# Main_BoardV2.net
KiCad netlist of a schematic drawn in EAGLE
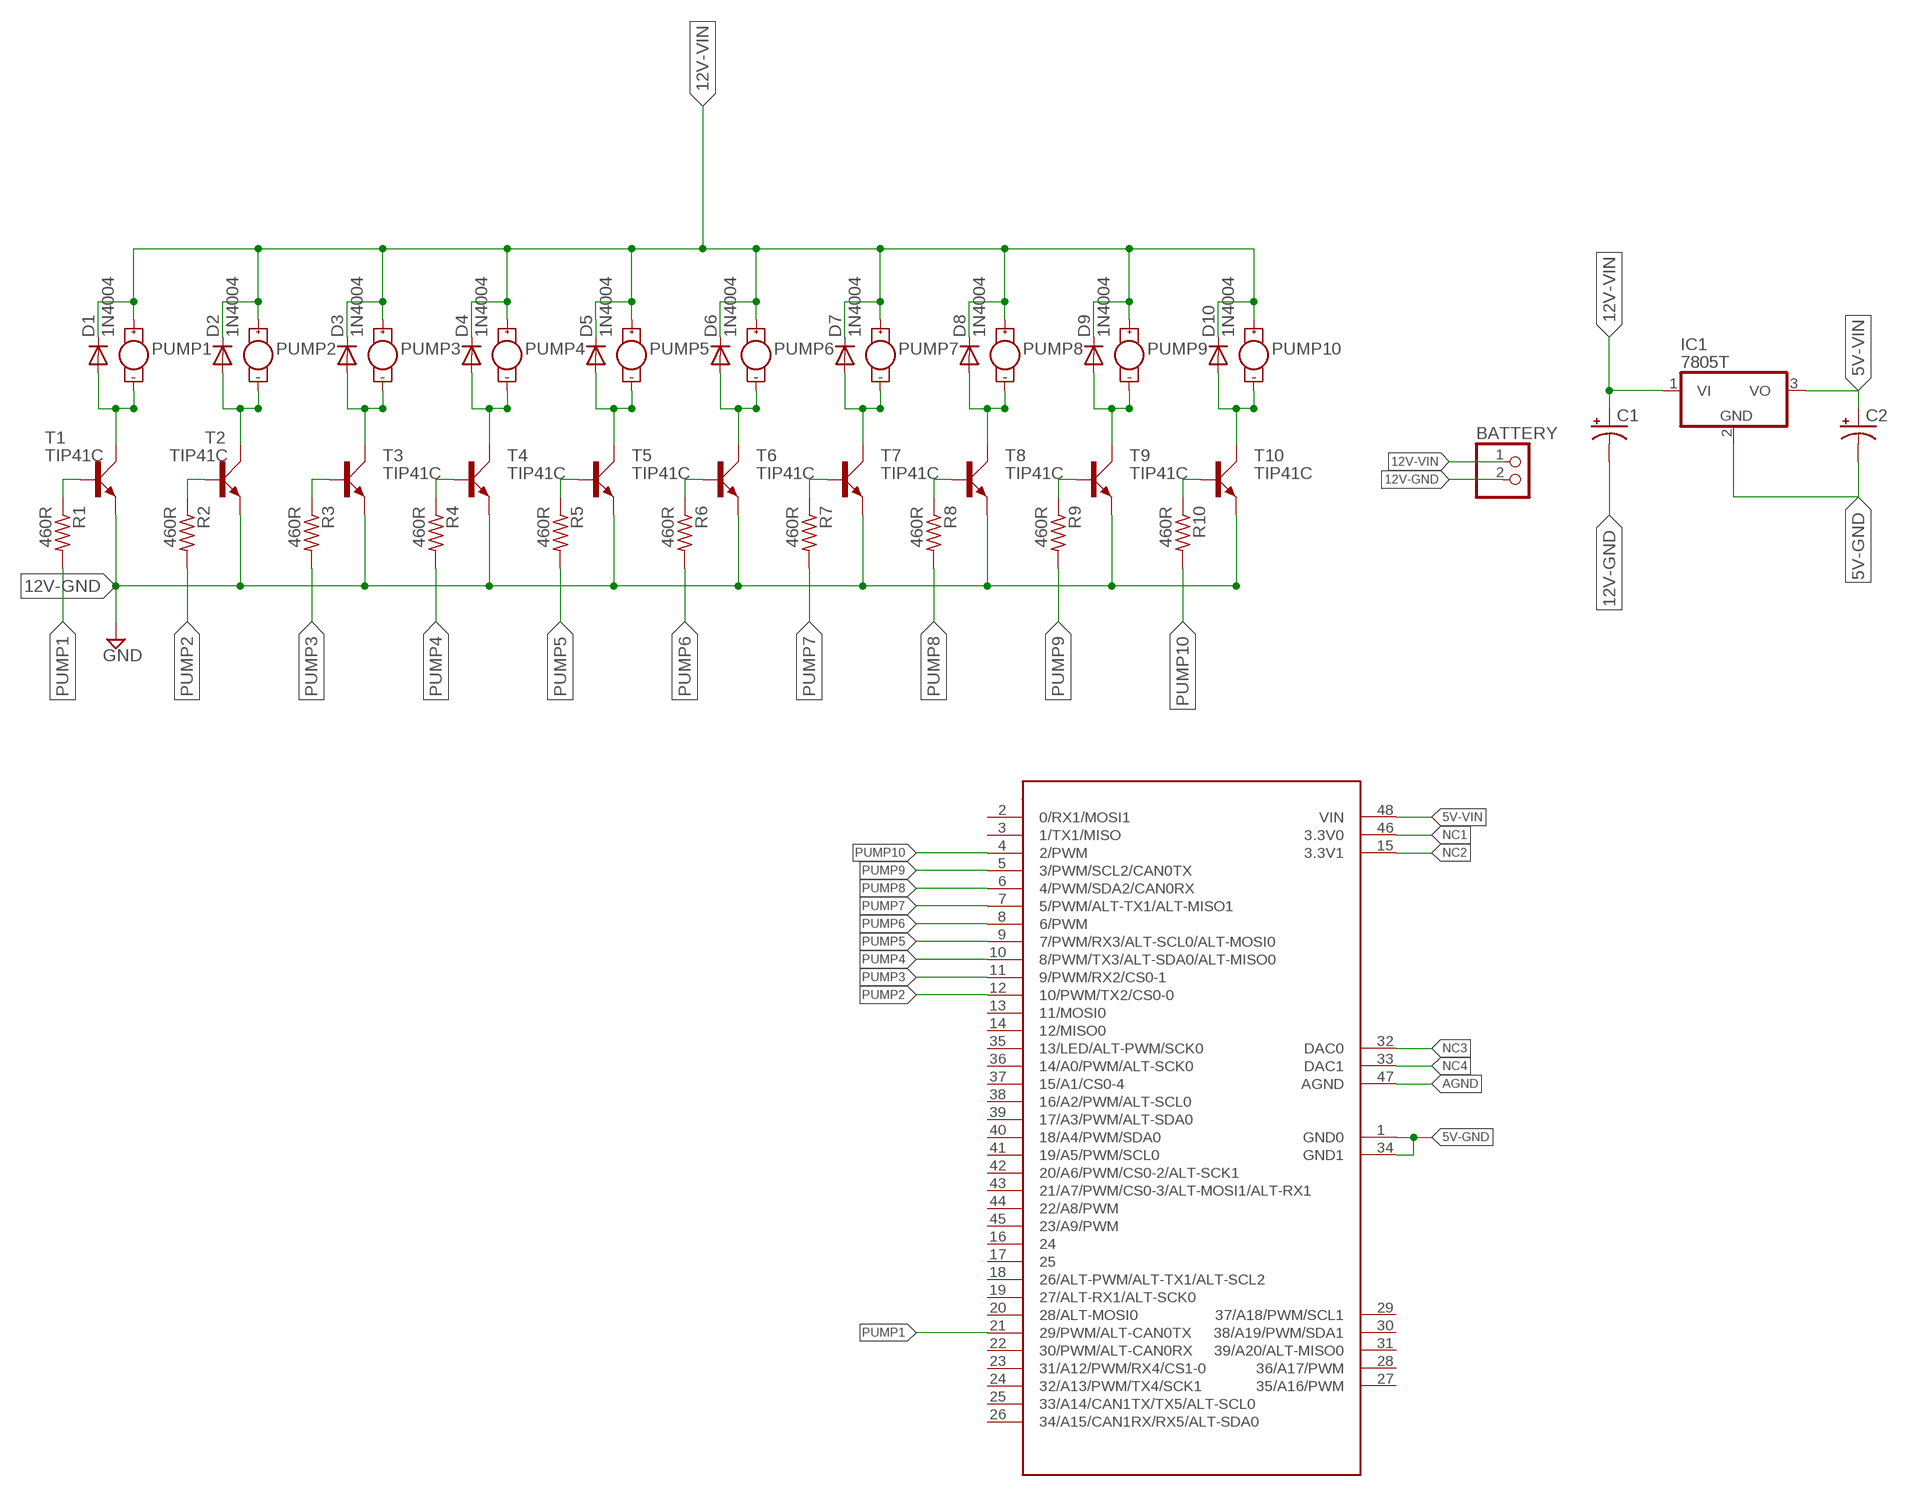
[diagram p0: schematic, sheet 1]

(export (version "E")
  (design (tool "Eeschema 10.0.6"))
  (components
    (comp (ref "BATTERY")
      (value "PINHD-1X2")
      (footprint "eagle-import:1X02")
      (fields (field (name "SPICEPREFIX") "B"))
      (libsource (lib "eagle-import") (part "PINHD-1X2"))
    )
    (comp (ref "C1")
      (value "CPOL-USE5-10.5")
      (footprint "eagle-import:E5-10,5")
      (libsource (lib "eagle-import") (part "CPOL-USE5-10.5"))
    )
    (comp (ref "C2")
      (value "CPOL-USE2.5-5")
      (footprint "eagle-import:E2,5-5")
      (libsource (lib "eagle-import") (part "CPOL-USE2.5-5"))
    )
    (comp (ref "D1")
      (value "1N4004")
      (footprint "eagle-import:DO41-10")
      (libsource (lib "eagle-import") (part "1N4004"))
    )
    (comp (ref "D2")
      (value "1N4004")
      (footprint "eagle-import:DO41-10")
      (libsource (lib "eagle-import") (part "1N4004"))
    )
    (comp (ref "D3")
      (value "1N4004")
      (footprint "eagle-import:DO41-10")
      (libsource (lib "eagle-import") (part "1N4004"))
    )
    (comp (ref "D4")
      (value "1N4004")
      (footprint "eagle-import:DO41-10")
      (libsource (lib "eagle-import") (part "1N4004"))
    )
    (comp (ref "D5")
      (value "1N4004")
      (footprint "eagle-import:DO41-10")
      (libsource (lib "eagle-import") (part "1N4004"))
    )
    (comp (ref "D6")
      (value "1N4004")
      (footprint "eagle-import:DO41-10")
      (libsource (lib "eagle-import") (part "1N4004"))
    )
    (comp (ref "D7")
      (value "1N4004")
      (footprint "eagle-import:DO41-10")
      (libsource (lib "eagle-import") (part "1N4004"))
    )
    (comp (ref "D8")
      (value "1N4004")
      (footprint "eagle-import:DO41-10")
      (libsource (lib "eagle-import") (part "1N4004"))
    )
    (comp (ref "D9")
      (value "1N4004")
      (footprint "eagle-import:DO41-10")
      (libsource (lib "eagle-import") (part "1N4004"))
    )
    (comp (ref "D10")
      (value "1N4004")
      (footprint "eagle-import:DO41-10")
      (libsource (lib "eagle-import") (part "1N4004"))
    )
    (comp (ref "IC1")
      (value "7805T")
      (footprint "eagle-import:TO220H")
      (libsource (lib "eagle-import") (part "78T05"))
    )
    (comp (ref "PUMP1")
      (value "PUMPS")
      (footprint "eagle-import:1X2_HEADER")
      (libsource (lib "eagle-import") (part "PUMPS"))
    )
    (comp (ref "PUMP2")
      (value "PUMPS")
      (footprint "eagle-import:1X2_HEADER")
      (libsource (lib "eagle-import") (part "PUMPS"))
    )
    (comp (ref "PUMP3")
      (value "PUMPS")
      (footprint "eagle-import:1X2_HEADER")
      (libsource (lib "eagle-import") (part "PUMPS"))
    )
    (comp (ref "PUMP4")
      (value "PUMPS")
      (footprint "eagle-import:1X2_HEADER")
      (libsource (lib "eagle-import") (part "PUMPS"))
    )
    (comp (ref "PUMP5")
      (value "PUMPS")
      (footprint "eagle-import:1X2_HEADER")
      (libsource (lib "eagle-import") (part "PUMPS"))
    )
    (comp (ref "PUMP6")
      (value "PUMPS")
      (footprint "eagle-import:1X2_HEADER")
      (libsource (lib "eagle-import") (part "PUMPS"))
    )
    (comp (ref "PUMP7")
      (value "PUMPS")
      (footprint "eagle-import:1X2_HEADER")
      (libsource (lib "eagle-import") (part "PUMPS"))
    )
    (comp (ref "PUMP8")
      (value "PUMPS")
      (footprint "eagle-import:1X2_HEADER")
      (libsource (lib "eagle-import") (part "PUMPS"))
    )
    (comp (ref "PUMP9")
      (value "PUMPS")
      (footprint "eagle-import:1X2_HEADER")
      (libsource (lib "eagle-import") (part "PUMPS"))
    )
    (comp (ref "PUMP10")
      (value "PUMPS")
      (footprint "eagle-import:1X2_HEADER")
      (libsource (lib "eagle-import") (part "PUMPS"))
    )
    (comp (ref "R1")
      (value "460R")
      (footprint "eagle-import:0805-THM")
      (libsource (lib "eagle-import") (part "R-US_FLIPFLOP"))
    )
    (comp (ref "R2")
      (value "460R")
      (footprint "eagle-import:0805-THM")
      (libsource (lib "eagle-import") (part "R-US_FLIPFLOP"))
    )
    (comp (ref "R3")
      (value "460R")
      (footprint "eagle-import:0805-THM")
      (libsource (lib "eagle-import") (part "R-US_FLIPFLOP"))
    )
    (comp (ref "R4")
      (value "460R")
      (footprint "eagle-import:0805-THM")
      (libsource (lib "eagle-import") (part "R-US_FLIPFLOP"))
    )
    (comp (ref "R5")
      (value "460R")
      (footprint "eagle-import:0805-THM")
      (libsource (lib "eagle-import") (part "R-US_FLIPFLOP"))
    )
    (comp (ref "R6")
      (value "460R")
      (footprint "eagle-import:0805-THM")
      (libsource (lib "eagle-import") (part "R-US_FLIPFLOP"))
    )
    (comp (ref "R7")
      (value "460R")
      (footprint "eagle-import:0805-THM")
      (libsource (lib "eagle-import") (part "R-US_FLIPFLOP"))
    )
    (comp (ref "R8")
      (value "460R")
      (footprint "eagle-import:0805-THM")
      (libsource (lib "eagle-import") (part "R-US_FLIPFLOP"))
    )
    (comp (ref "R9")
      (value "460R")
      (footprint "eagle-import:0805-THM")
      (libsource (lib "eagle-import") (part "R-US_FLIPFLOP"))
    )
    (comp (ref "R10")
      (value "460R")
      (footprint "eagle-import:0805-THM")
      (libsource (lib "eagle-import") (part "R-US_FLIPFLOP"))
    )
    (comp (ref "T1")
      (value "TIP41C")
      (footprint "eagle-import:TO220AV")
      (libsource (lib "eagle-import") (part "TIP41C"))
    )
    (comp (ref "T2")
      (value "TIP41C")
      (footprint "eagle-import:TO220AV")
      (libsource (lib "eagle-import") (part "TIP41C"))
    )
    (comp (ref "T3")
      (value "TIP41C")
      (footprint "eagle-import:TO220AV")
      (libsource (lib "eagle-import") (part "TIP41C"))
    )
    (comp (ref "T4")
      (value "TIP41C")
      (footprint "eagle-import:TO220AV")
      (libsource (lib "eagle-import") (part "TIP41C"))
    )
    (comp (ref "T5")
      (value "TIP41C")
      (footprint "eagle-import:TO220AV")
      (libsource (lib "eagle-import") (part "TIP41C"))
    )
    (comp (ref "T6")
      (value "TIP41C")
      (footprint "eagle-import:TO220AV")
      (libsource (lib "eagle-import") (part "TIP41C"))
    )
    (comp (ref "T7")
      (value "TIP41C")
      (footprint "eagle-import:TO220AV")
      (libsource (lib "eagle-import") (part "TIP41C"))
    )
    (comp (ref "T8")
      (value "TIP41C")
      (footprint "eagle-import:TO220AV")
      (libsource (lib "eagle-import") (part "TIP41C"))
    )
    (comp (ref "T9")
      (value "TIP41C")
      (footprint "eagle-import:TO220AV")
      (libsource (lib "eagle-import") (part "TIP41C"))
    )
    (comp (ref "T10")
      (value "TIP41C")
      (footprint "eagle-import:TO220AV")
      (libsource (lib "eagle-import") (part "TIP41C"))
    )
    (comp (ref "TEENSY1")
      (value "TEENSY_3.5")
      (footprint "eagle-import:DIP1524W60P254L6350H635Q48A")
      (libsource (lib "eagle-import") (part "TEENSY_3.5"))
    )
  )
  (nets
    (net (code "1") (name "5V-GND") (class "Default")
      (node (ref "C2") (pin "-") (pinfunction "-_-") (pintype "passive"))
      (node (ref "IC1") (pin "2") (pinfunction "GND_2") (pintype "passive"))
      (node (ref "TEENSY1") (pin "1") (pinfunction "GND0_1") (pintype "power_in"))
      (node (ref "TEENSY1") (pin "34") (pinfunction "GND1_34") (pintype "power_in"))
    )
    (net (code "2") (name "5V-VIN") (class "Default")
      (node (ref "C2") (pin "+") (pinfunction "+_+") (pintype "passive"))
      (node (ref "IC1") (pin "3") (pinfunction "VO_3") (pintype "passive"))
      (node (ref "TEENSY1") (pin "48") (pinfunction "VIN_48") (pintype "power_in"))
    )
    (net (code "3") (name "12V-GND") (class "Default")
      (node (ref "BATTERY") (pin "2") (pinfunction "2_2") (pintype "passive"))
      (node (ref "C1") (pin "-") (pinfunction "-_-") (pintype "passive"))
      (node (ref "T1") (pin "E") (pinfunction "E_E") (pintype "passive"))
      (node (ref "T10") (pin "E") (pinfunction "E_E") (pintype "passive"))
      (node (ref "T2") (pin "E") (pinfunction "E_E") (pintype "passive"))
      (node (ref "T3") (pin "E") (pinfunction "E_E") (pintype "passive"))
      (node (ref "T4") (pin "E") (pinfunction "E_E") (pintype "passive"))
      (node (ref "T5") (pin "E") (pinfunction "E_E") (pintype "passive"))
      (node (ref "T6") (pin "E") (pinfunction "E_E") (pintype "passive"))
      (node (ref "T7") (pin "E") (pinfunction "E_E") (pintype "passive"))
      (node (ref "T8") (pin "E") (pinfunction "E_E") (pintype "passive"))
      (node (ref "T9") (pin "E") (pinfunction "E_E") (pintype "passive"))
    )
    (net (code "4") (name "12V-VIN") (class "Default")
      (node (ref "BATTERY") (pin "1") (pinfunction "1_1") (pintype "passive"))
      (node (ref "C1") (pin "+") (pinfunction "+_+") (pintype "passive"))
      (node (ref "D1") (pin "C") (pinfunction "C_C") (pintype "passive"))
      (node (ref "D10") (pin "C") (pinfunction "C_C") (pintype "passive"))
      (node (ref "D2") (pin "C") (pinfunction "C_C") (pintype "passive"))
      (node (ref "D3") (pin "C") (pinfunction "C_C") (pintype "passive"))
      (node (ref "D4") (pin "C") (pinfunction "C_C") (pintype "passive"))
      (node (ref "D5") (pin "C") (pinfunction "C_C") (pintype "passive"))
      (node (ref "D6") (pin "C") (pinfunction "C_C") (pintype "passive"))
      (node (ref "D7") (pin "C") (pinfunction "C_C") (pintype "passive"))
      (node (ref "D8") (pin "C") (pinfunction "C_C") (pintype "passive"))
      (node (ref "D9") (pin "C") (pinfunction "C_C") (pintype "passive"))
      (node (ref "IC1") (pin "1") (pinfunction "VI_1") (pintype "input"))
      (node (ref "PUMP1") (pin "1") (pinfunction "+_1") (pintype "bidirectional"))
      (node (ref "PUMP10") (pin "1") (pinfunction "+_1") (pintype "bidirectional"))
      (node (ref "PUMP2") (pin "1") (pinfunction "+_1") (pintype "bidirectional"))
      (node (ref "PUMP3") (pin "1") (pinfunction "+_1") (pintype "bidirectional"))
      (node (ref "PUMP4") (pin "1") (pinfunction "+_1") (pintype "bidirectional"))
      (node (ref "PUMP5") (pin "1") (pinfunction "+_1") (pintype "bidirectional"))
      (node (ref "PUMP6") (pin "1") (pinfunction "+_1") (pintype "bidirectional"))
      (node (ref "PUMP7") (pin "1") (pinfunction "+_1") (pintype "bidirectional"))
      (node (ref "PUMP8") (pin "1") (pinfunction "+_1") (pintype "bidirectional"))
      (node (ref "PUMP9") (pin "1") (pinfunction "+_1") (pintype "bidirectional"))
    )
    (net (code "5") (name "AGND") (class "Default")
      (node (ref "TEENSY1") (pin "47") (pinfunction "AGND_47") (pintype "power_in"))
    )
    (net (code "6") (name "NC1") (class "Default")
      (node (ref "TEENSY1") (pin "46") (pinfunction "3.3V0_46") (pintype "power_in"))
    )
    (net (code "7") (name "NC2") (class "Default")
      (node (ref "TEENSY1") (pin "15") (pinfunction "3.3V1_15") (pintype "power_in"))
    )
    (net (code "8") (name "NC3") (class "Default")
      (node (ref "TEENSY1") (pin "32") (pinfunction "DAC0_32") (pintype "bidirectional"))
    )
    (net (code "9") (name "NC4") (class "Default")
      (node (ref "TEENSY1") (pin "33") (pinfunction "DAC1_33") (pintype "bidirectional"))
    )
    (net (code "10") (name "Net-(PUMP1--)") (class "Default")
      (node (ref "D1") (pin "A") (pinfunction "A_A") (pintype "passive"))
      (node (ref "PUMP1") (pin "2") (pinfunction "-_2") (pintype "bidirectional"))
      (node (ref "T1") (pin "C") (pinfunction "C_C") (pintype "passive"))
    )
    (net (code "11") (name "Net-(PUMP2--)") (class "Default")
      (node (ref "D2") (pin "A") (pinfunction "A_A") (pintype "passive"))
      (node (ref "PUMP2") (pin "2") (pinfunction "-_2") (pintype "bidirectional"))
      (node (ref "T2") (pin "C") (pinfunction "C_C") (pintype "passive"))
    )
    (net (code "12") (name "Net-(PUMP3--)") (class "Default")
      (node (ref "D3") (pin "A") (pinfunction "A_A") (pintype "passive"))
      (node (ref "PUMP3") (pin "2") (pinfunction "-_2") (pintype "bidirectional"))
      (node (ref "T3") (pin "C") (pinfunction "C_C") (pintype "passive"))
    )
    (net (code "13") (name "Net-(PUMP4--)") (class "Default")
      (node (ref "D4") (pin "A") (pinfunction "A_A") (pintype "passive"))
      (node (ref "PUMP4") (pin "2") (pinfunction "-_2") (pintype "bidirectional"))
      (node (ref "T4") (pin "C") (pinfunction "C_C") (pintype "passive"))
    )
    (net (code "14") (name "Net-(PUMP5--)") (class "Default")
      (node (ref "D5") (pin "A") (pinfunction "A_A") (pintype "passive"))
      (node (ref "PUMP5") (pin "2") (pinfunction "-_2") (pintype "bidirectional"))
      (node (ref "T5") (pin "C") (pinfunction "C_C") (pintype "passive"))
    )
    (net (code "15") (name "Net-(PUMP6--)") (class "Default")
      (node (ref "D6") (pin "A") (pinfunction "A_A") (pintype "passive"))
      (node (ref "PUMP6") (pin "2") (pinfunction "-_2") (pintype "bidirectional"))
      (node (ref "T6") (pin "C") (pinfunction "C_C") (pintype "passive"))
    )
    (net (code "16") (name "Net-(PUMP7--)") (class "Default")
      (node (ref "D7") (pin "A") (pinfunction "A_A") (pintype "passive"))
      (node (ref "PUMP7") (pin "2") (pinfunction "-_2") (pintype "bidirectional"))
      (node (ref "T7") (pin "C") (pinfunction "C_C") (pintype "passive"))
    )
    (net (code "17") (name "Net-(PUMP8--)") (class "Default")
      (node (ref "D8") (pin "A") (pinfunction "A_A") (pintype "passive"))
      (node (ref "PUMP8") (pin "2") (pinfunction "-_2") (pintype "bidirectional"))
      (node (ref "T8") (pin "C") (pinfunction "C_C") (pintype "passive"))
    )
    (net (code "18") (name "Net-(PUMP9--)") (class "Default")
      (node (ref "D9") (pin "A") (pinfunction "A_A") (pintype "passive"))
      (node (ref "PUMP9") (pin "2") (pinfunction "-_2") (pintype "bidirectional"))
      (node (ref "T9") (pin "C") (pinfunction "C_C") (pintype "passive"))
    )
    (net (code "19") (name "Net-(PUMP10--)") (class "Default")
      (node (ref "D10") (pin "A") (pinfunction "A_A") (pintype "passive"))
      (node (ref "PUMP10") (pin "2") (pinfunction "-_2") (pintype "bidirectional"))
      (node (ref "T10") (pin "C") (pinfunction "C_C") (pintype "passive"))
    )
    (net (code "20") (name "Net-(R1-Pad1)") (class "Default")
      (node (ref "R1") (pin "1") (pinfunction "1_1") (pintype "passive"))
      (node (ref "T1") (pin "B") (pinfunction "B_B") (pintype "passive"))
    )
    (net (code "21") (name "Net-(R2-Pad1)") (class "Default")
      (node (ref "R2") (pin "1") (pinfunction "1_1") (pintype "passive"))
      (node (ref "T2") (pin "B") (pinfunction "B_B") (pintype "passive"))
    )
    (net (code "22") (name "Net-(R3-Pad1)") (class "Default")
      (node (ref "R3") (pin "1") (pinfunction "1_1") (pintype "passive"))
      (node (ref "T3") (pin "B") (pinfunction "B_B") (pintype "passive"))
    )
    (net (code "23") (name "Net-(R4-Pad1)") (class "Default")
      (node (ref "R4") (pin "1") (pinfunction "1_1") (pintype "passive"))
      (node (ref "T4") (pin "B") (pinfunction "B_B") (pintype "passive"))
    )
    (net (code "24") (name "Net-(R5-Pad1)") (class "Default")
      (node (ref "R5") (pin "1") (pinfunction "1_1") (pintype "passive"))
      (node (ref "T5") (pin "B") (pinfunction "B_B") (pintype "passive"))
    )
    (net (code "25") (name "Net-(R6-Pad1)") (class "Default")
      (node (ref "R6") (pin "1") (pinfunction "1_1") (pintype "passive"))
      (node (ref "T6") (pin "B") (pinfunction "B_B") (pintype "passive"))
    )
    (net (code "26") (name "Net-(R7-Pad1)") (class "Default")
      (node (ref "R7") (pin "1") (pinfunction "1_1") (pintype "passive"))
      (node (ref "T7") (pin "B") (pinfunction "B_B") (pintype "passive"))
    )
    (net (code "27") (name "Net-(R8-Pad1)") (class "Default")
      (node (ref "R8") (pin "1") (pinfunction "1_1") (pintype "passive"))
      (node (ref "T8") (pin "B") (pinfunction "B_B") (pintype "passive"))
    )
    (net (code "28") (name "Net-(R9-Pad1)") (class "Default")
      (node (ref "R9") (pin "1") (pinfunction "1_1") (pintype "passive"))
      (node (ref "T9") (pin "B") (pinfunction "B_B") (pintype "passive"))
    )
    (net (code "29") (name "Net-(R10-Pad1)") (class "Default")
      (node (ref "R10") (pin "1") (pinfunction "1_1") (pintype "passive"))
      (node (ref "T10") (pin "B") (pinfunction "B_B") (pintype "passive"))
    )
    (net (code "30") (name "PUMP1") (class "Default")
      (node (ref "R1") (pin "2") (pinfunction "2_2") (pintype "passive"))
      (node (ref "TEENSY1") (pin "21") (pinfunction "29/PWM/ALT-CAN0TX_21") (pintype "bidirectional"))
    )
    (net (code "31") (name "PUMP2") (class "Default")
      (node (ref "R2") (pin "2") (pinfunction "2_2") (pintype "passive"))
      (node (ref "TEENSY1") (pin "12") (pinfunction "10/PWM/TX2/CS0-0_12") (pintype "bidirectional"))
    )
    (net (code "32") (name "PUMP3") (class "Default")
      (node (ref "R3") (pin "2") (pinfunction "2_2") (pintype "passive"))
      (node (ref "TEENSY1") (pin "11") (pinfunction "9/PWM/RX2/CS0-1_11") (pintype "bidirectional"))
    )
    (net (code "33") (name "PUMP4") (class "Default")
      (node (ref "R4") (pin "2") (pinfunction "2_2") (pintype "passive"))
      (node (ref "TEENSY1") (pin "10") (pinfunction "8/PWM/TX3/ALT-SDA0/ALT-MISO0_10") (pintype "bidirectional"))
    )
    (net (code "34") (name "PUMP5") (class "Default")
      (node (ref "R5") (pin "2") (pinfunction "2_2") (pintype "passive"))
      (node (ref "TEENSY1") (pin "9") (pinfunction "7/PWM/RX3/ALT-SCL0/ALT-MOSI0_9") (pintype "bidirectional"))
    )
    (net (code "35") (name "PUMP6") (class "Default")
      (node (ref "R6") (pin "2") (pinfunction "2_2") (pintype "passive"))
      (node (ref "TEENSY1") (pin "8") (pinfunction "6/PWM_8") (pintype "bidirectional"))
    )
    (net (code "36") (name "PUMP7") (class "Default")
      (node (ref "R7") (pin "2") (pinfunction "2_2") (pintype "passive"))
      (node (ref "TEENSY1") (pin "7") (pinfunction "5/PWM/ALT-TX1/ALT-MISO1_7") (pintype "bidirectional"))
    )
    (net (code "37") (name "PUMP8") (class "Default")
      (node (ref "R8") (pin "2") (pinfunction "2_2") (pintype "passive"))
      (node (ref "TEENSY1") (pin "6") (pinfunction "4/PWM/SDA2/CAN0RX_6") (pintype "bidirectional"))
    )
    (net (code "38") (name "PUMP9") (class "Default")
      (node (ref "R9") (pin "2") (pinfunction "2_2") (pintype "passive"))
      (node (ref "TEENSY1") (pin "5") (pinfunction "3/PWM/SCL2/CAN0TX_5") (pintype "bidirectional"))
    )
    (net (code "39") (name "PUMP10") (class "Default")
      (node (ref "R10") (pin "2") (pinfunction "2_2") (pintype "passive"))
      (node (ref "TEENSY1") (pin "4") (pinfunction "2/PWM_4") (pintype "bidirectional"))
    )
    (net (code "40") (name "unconnected-(TEENSY1-0{slash}RX1{slash}MOSI1-Pad2)") (class "Default")
      (node (ref "TEENSY1") (pin "2") (pinfunction "0/RX1/MOSI1_2") (pintype "bidirectional"))
    )
    (net (code "41") (name "unconnected-(TEENSY1-1{slash}TX1{slash}MISO-Pad3)") (class "Default")
      (node (ref "TEENSY1") (pin "3") (pinfunction "1/TX1/MISO_3") (pintype "bidirectional"))
    )
    (net (code "42") (name "unconnected-(TEENSY1-11{slash}MOSI0-Pad13)") (class "Default")
      (node (ref "TEENSY1") (pin "13") (pinfunction "11/MOSI0_13") (pintype "bidirectional"))
    )
    (net (code "43") (name "unconnected-(TEENSY1-12{slash}MISO0-Pad14)") (class "Default")
      (node (ref "TEENSY1") (pin "14") (pinfunction "12/MISO0_14") (pintype "bidirectional"))
    )
    (net (code "44") (name "unconnected-(TEENSY1-13{slash}LED{slash}ALT-PWM{slash}SCK0-Pad35)") (class "Default")
      (node (ref "TEENSY1") (pin "35") (pinfunction "13/LED/ALT-PWM/SCK0_35") (pintype "bidirectional"))
    )
    (net (code "45") (name "unconnected-(TEENSY1-14{slash}A0{slash}PWM{slash}ALT-SCK0-Pad36)") (class "Default")
      (node (ref "TEENSY1") (pin "36") (pinfunction "14/A0/PWM/ALT-SCK0_36") (pintype "bidirectional"))
    )
    (net (code "46") (name "unconnected-(TEENSY1-15{slash}A1{slash}CS0-4-Pad37)") (class "Default")
      (node (ref "TEENSY1") (pin "37") (pinfunction "15/A1/CS0-4_37") (pintype "bidirectional"))
    )
    (net (code "47") (name "unconnected-(TEENSY1-16{slash}A2{slash}PWM{slash}ALT-SCL0-Pad38)") (class "Default")
      (node (ref "TEENSY1") (pin "38") (pinfunction "16/A2/PWM/ALT-SCL0_38") (pintype "bidirectional"))
    )
    (net (code "48") (name "unconnected-(TEENSY1-17{slash}A3{slash}PWM{slash}ALT-SDA0-Pad39)") (class "Default")
      (node (ref "TEENSY1") (pin "39") (pinfunction "17/A3/PWM/ALT-SDA0_39") (pintype "bidirectional"))
    )
    (net (code "49") (name "unconnected-(TEENSY1-18{slash}A4{slash}PWM{slash}SDA0-Pad40)") (class "Default")
      (node (ref "TEENSY1") (pin "40") (pinfunction "18/A4/PWM/SDA0_40") (pintype "bidirectional"))
    )
    (net (code "50") (name "unconnected-(TEENSY1-19{slash}A5{slash}PWM{slash}SCL0-Pad41)") (class "Default")
      (node (ref "TEENSY1") (pin "41") (pinfunction "19/A5/PWM/SCL0_41") (pintype "bidirectional"))
    )
    (net (code "51") (name "unconnected-(TEENSY1-20{slash}A6{slash}PWM{slash}CS0-2{slash}ALT-SCK1-Pad42)") (class "Default")
      (node (ref "TEENSY1") (pin "42") (pinfunction "20/A6/PWM/CS0-2/ALT-SCK1_42") (pintype "bidirectional"))
    )
    (net (code "52") (name "unconnected-(TEENSY1-21{slash}A7{slash}PWM{slash}CS0-3{slash}ALT-MOSI1{slash}ALT-RX1-Pad43)") (class "Default")
      (node (ref "TEENSY1") (pin "43") (pinfunction "21/A7/PWM/CS0-3/ALT-MOSI1/ALT-RX1_43") (pintype "bidirectional"))
    )
    (net (code "53") (name "unconnected-(TEENSY1-22{slash}A8{slash}PWM-Pad44)") (class "Default")
      (node (ref "TEENSY1") (pin "44") (pinfunction "22/A8/PWM_44") (pintype "bidirectional"))
    )
    (net (code "54") (name "unconnected-(TEENSY1-23{slash}A9{slash}PWM-Pad45)") (class "Default")
      (node (ref "TEENSY1") (pin "45") (pinfunction "23/A9/PWM_45") (pintype "bidirectional"))
    )
    (net (code "55") (name "unconnected-(TEENSY1-24-Pad16)") (class "Default")
      (node (ref "TEENSY1") (pin "16") (pinfunction "24_16") (pintype "bidirectional"))
    )
    (net (code "56") (name "unconnected-(TEENSY1-25-Pad17)") (class "Default")
      (node (ref "TEENSY1") (pin "17") (pinfunction "25_17") (pintype "bidirectional"))
    )
    (net (code "57") (name "unconnected-(TEENSY1-26{slash}ALT-PWM{slash}ALT-TX1{slash}ALT-SCL2-Pad18)") (class "Default")
      (node (ref "TEENSY1") (pin "18") (pinfunction "26/ALT-PWM/ALT-TX1/ALT-SCL2_18") (pintype "bidirectional"))
    )
    (net (code "58") (name "unconnected-(TEENSY1-27{slash}ALT-RX1{slash}ALT-SCK0-Pad19)") (class "Default")
      (node (ref "TEENSY1") (pin "19") (pinfunction "27/ALT-RX1/ALT-SCK0_19") (pintype "bidirectional"))
    )
    (net (code "59") (name "unconnected-(TEENSY1-28{slash}ALT-MOSI0-Pad20)") (class "Default")
      (node (ref "TEENSY1") (pin "20") (pinfunction "28/ALT-MOSI0_20") (pintype "bidirectional"))
    )
    (net (code "60") (name "unconnected-(TEENSY1-30{slash}PWM{slash}ALT-CAN0RX-Pad22)") (class "Default")
      (node (ref "TEENSY1") (pin "22") (pinfunction "30/PWM/ALT-CAN0RX_22") (pintype "bidirectional"))
    )
    (net (code "61") (name "unconnected-(TEENSY1-31{slash}A12{slash}PWM{slash}RX4{slash}CS1-0-Pad23)") (class "Default")
      (node (ref "TEENSY1") (pin "23") (pinfunction "31/A12/PWM/RX4/CS1-0_23") (pintype "bidirectional"))
    )
    (net (code "62") (name "unconnected-(TEENSY1-32{slash}A13{slash}PWM{slash}TX4{slash}SCK1-Pad24)") (class "Default")
      (node (ref "TEENSY1") (pin "24") (pinfunction "32/A13/PWM/TX4/SCK1_24") (pintype "bidirectional"))
    )
    (net (code "63") (name "unconnected-(TEENSY1-33{slash}A14{slash}CAN1TX{slash}TX5{slash}ALT-SCL0-Pad25)") (class "Default")
      (node (ref "TEENSY1") (pin "25") (pinfunction "33/A14/CAN1TX/TX5/ALT-SCL0_25") (pintype "bidirectional"))
    )
    (net (code "64") (name "unconnected-(TEENSY1-34{slash}A15{slash}CAN1RX{slash}RX5{slash}ALT-SDA0-Pad26)") (class "Default")
      (node (ref "TEENSY1") (pin "26") (pinfunction "34/A15/CAN1RX/RX5/ALT-SDA0_26") (pintype "bidirectional"))
    )
    (net (code "65") (name "unconnected-(TEENSY1-35{slash}A16{slash}PWM-Pad27)") (class "Default")
      (node (ref "TEENSY1") (pin "27") (pinfunction "35/A16/PWM_27") (pintype "bidirectional"))
    )
    (net (code "66") (name "unconnected-(TEENSY1-36{slash}A17{slash}PWM-Pad28)") (class "Default")
      (node (ref "TEENSY1") (pin "28") (pinfunction "36/A17/PWM_28") (pintype "bidirectional"))
    )
    (net (code "67") (name "unconnected-(TEENSY1-37{slash}A18{slash}PWM{slash}SCL1-Pad29)") (class "Default")
      (node (ref "TEENSY1") (pin "29") (pinfunction "37/A18/PWM/SCL1_29") (pintype "bidirectional"))
    )
    (net (code "68") (name "unconnected-(TEENSY1-38{slash}A19{slash}PWM{slash}SDA1-Pad30)") (class "Default")
      (node (ref "TEENSY1") (pin "30") (pinfunction "38/A19/PWM/SDA1_30") (pintype "bidirectional"))
    )
    (net (code "69") (name "unconnected-(TEENSY1-39{slash}A20{slash}ALT-MISO0-Pad31)") (class "Default")
      (node (ref "TEENSY1") (pin "31") (pinfunction "39/A20/ALT-MISO0_31") (pintype "bidirectional"))
    )
  )
)
